# CH32V467RET-R0.net
KiCad netlist of a schematic drawn in Altium Designer
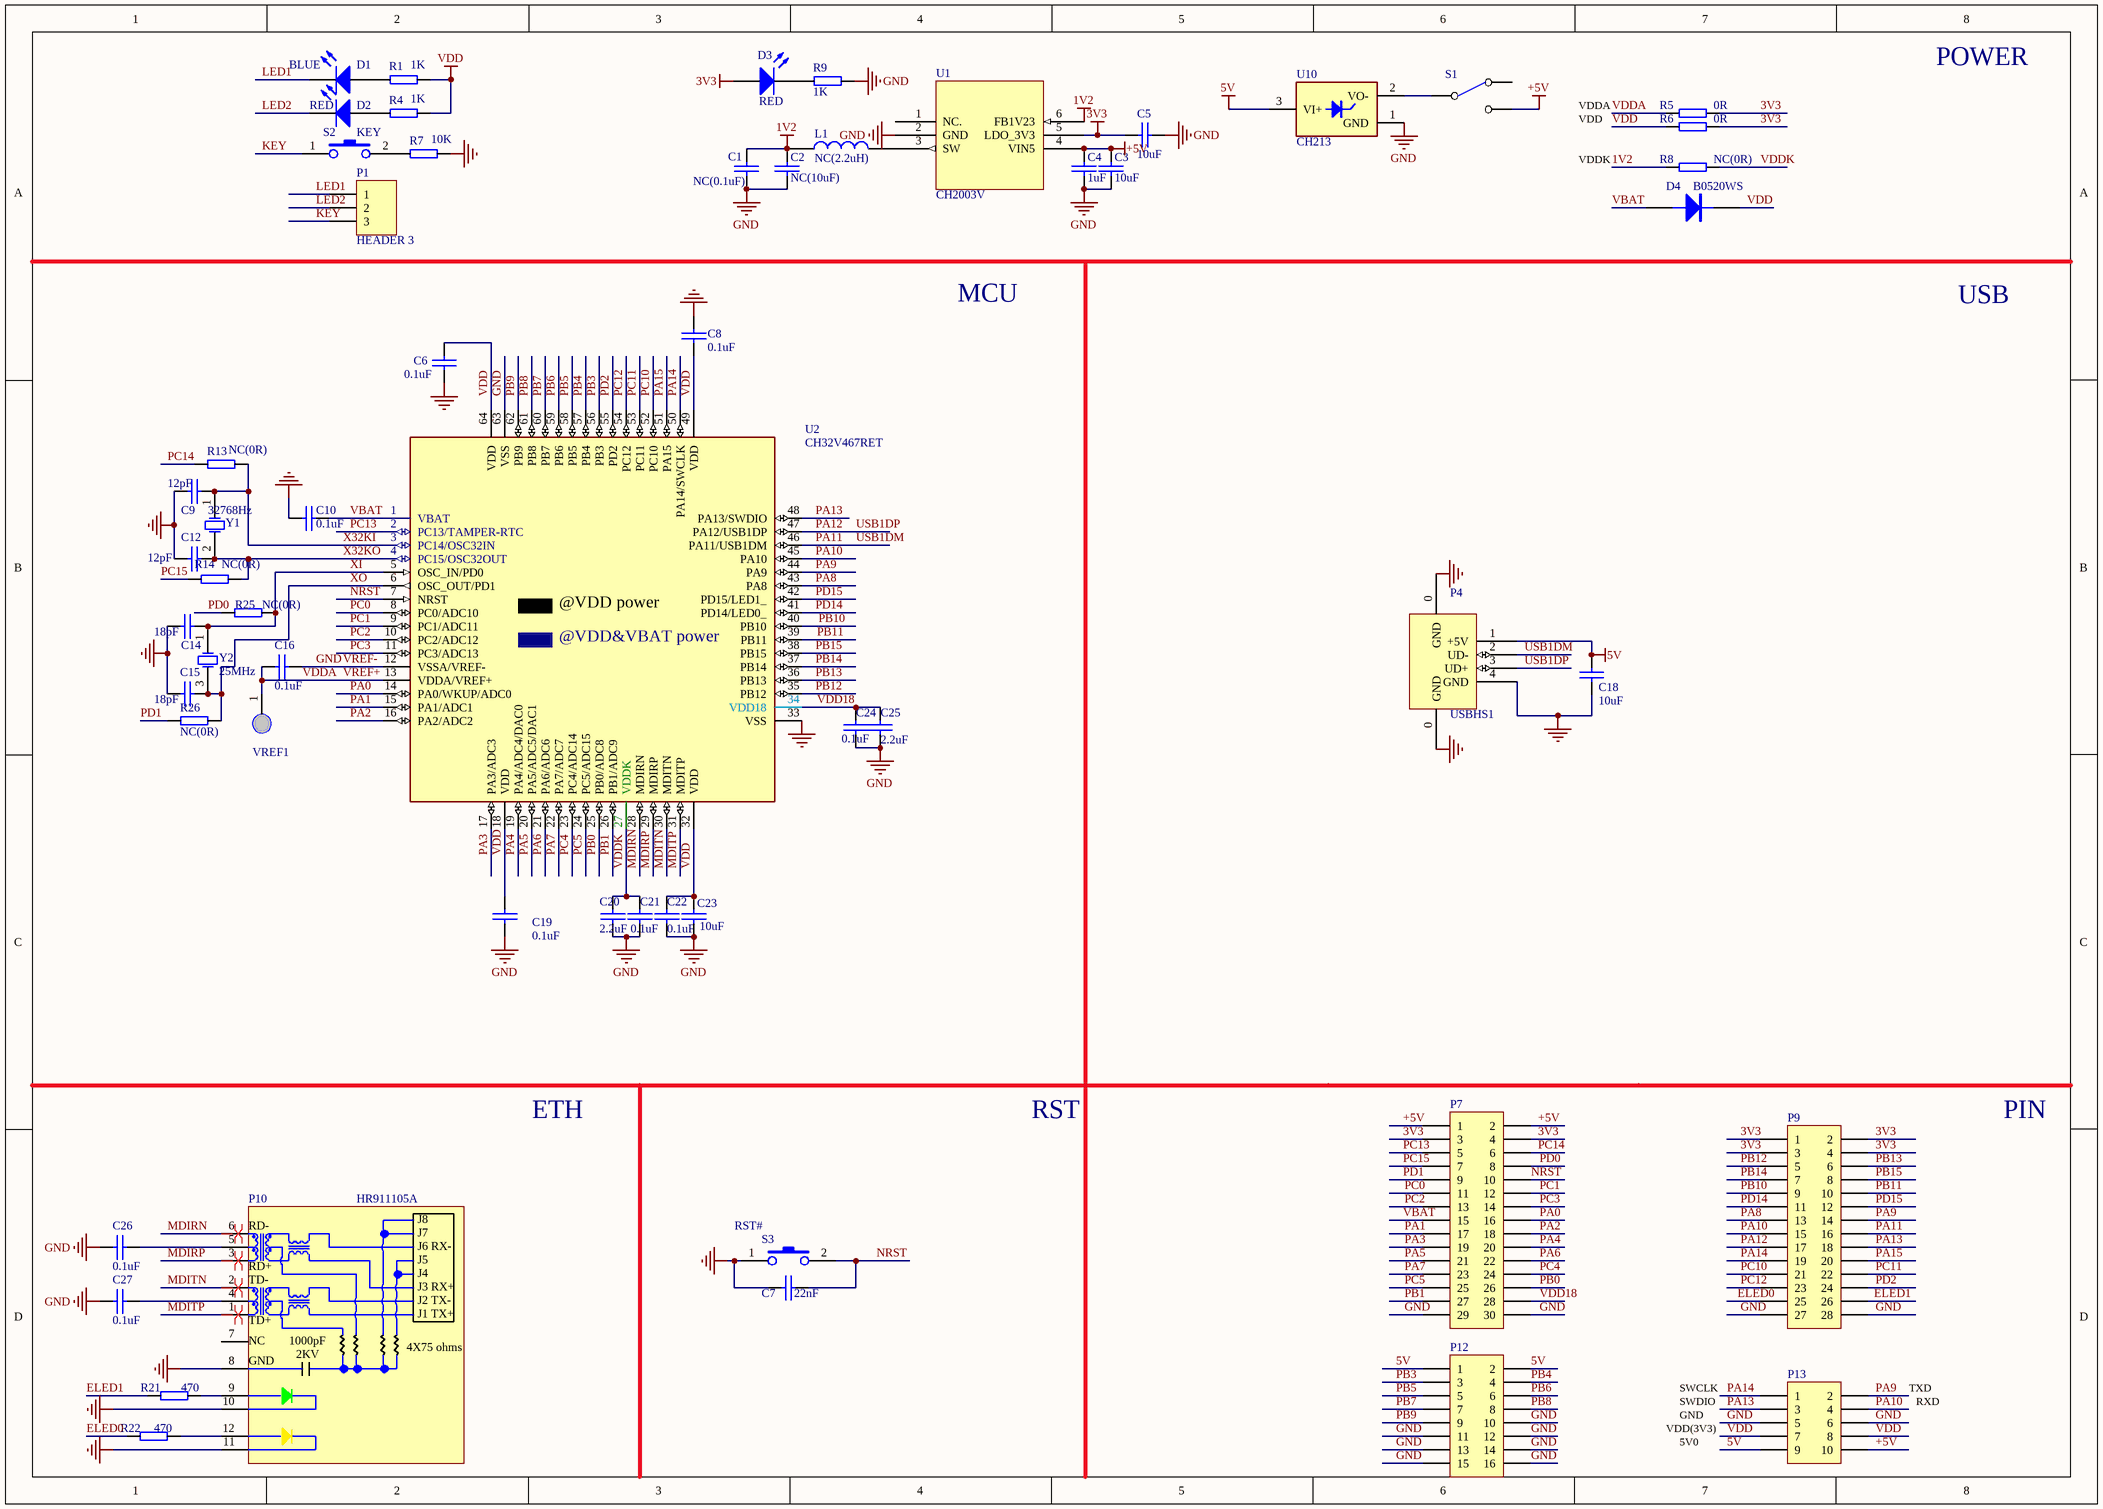
[diagram p0: CH32V467RET-R0.SchDoc]

(export (version "E")
  (design (tool "Eeschema 10.0.6"))
  (components
    (comp (ref "C1")
      (value "NC(0.1uF)")
      (footprint "0402_C")
      (description "Capacitor")
      (libsource (lib "") (part "CAP_1"))
    )
    (comp (ref "C2")
      (value "NC(10uF)")
      (footprint "0603_C")
      (description "Capacitor")
      (libsource (lib "*") (part "CAP"))
    )
    (comp (ref "C3")
      (value "10uF")
      (footprint "0603_C")
      (description "Capacitor")
      (libsource (lib "*") (part "CAP"))
    )
    (comp (ref "C4")
      (value "1uF")
      (footprint "0402_C")
      (description "Capacitor")
      (libsource (lib "") (part "CAP_1"))
    )
    (comp (ref "C5")
      (value "10uF")
      (footprint "0603_C")
      (description "Capacitor")
      (libsource (lib "*") (part "CAP"))
    )
    (comp (ref "C6")
      (value "0.1uF")
      (footprint "0402_C")
      (description "Capacitor")
      (libsource (lib "*") (part "CAP"))
    )
    (comp (ref "C7")
      (value "22nF")
      (footprint "0402_C")
      (description "Capacitor")
      (libsource (lib "") (part "CAP_2"))
    )
    (comp (ref "C8")
      (value "0.1uF")
      (footprint "0402_C")
      (description "Capacitor")
      (libsource (lib "*") (part "CAP"))
    )
    (comp (ref "C9")
      (value "12pF")
      (footprint "0402_C")
      (description "Capacitor")
      (libsource (lib "*") (part "CAP"))
    )
    (comp (ref "C10")
      (value "0.1uF")
      (footprint "0402_C")
      (description "Capacitor")
      (libsource (lib "*") (part "CAP"))
    )
    (comp (ref "C12")
      (value "12pF")
      (footprint "0402_C")
      (description "Capacitor")
      (libsource (lib "*") (part "CAP"))
    )
    (comp (ref "C14")
      (value "18pF")
      (footprint "0402_C")
      (description "Capacitor")
      (libsource (lib "*") (part "CAP"))
    )
    (comp (ref "C15")
      (value "18pF")
      (footprint "0402_C")
      (description "Capacitor")
      (libsource (lib "*") (part "CAP"))
    )
    (comp (ref "C16")
      (value "0.1uF")
      (footprint "0402_C")
      (description "Capacitor")
      (libsource (lib "*") (part "CAP"))
    )
    (comp (ref "C18")
      (value "10uF")
      (footprint "0603_C")
      (description "Capacitor")
      (libsource (lib "") (part "CAP_2"))
    )
    (comp (ref "C19")
      (value "0.1uF")
      (footprint "0402_C")
      (description "Capacitor")
      (libsource (lib "*") (part "CAP"))
    )
    (comp (ref "C20")
      (value "2.2uF")
      (footprint "0402_C")
      (description "Capacitor")
      (libsource (lib "*") (part "CAP"))
    )
    (comp (ref "C21")
      (value "0.1uF")
      (footprint "0402_C")
      (description "Capacitor")
      (libsource (lib "*") (part "CAP"))
    )
    (comp (ref "C22")
      (value "0.1uF")
      (footprint "0402_C")
      (description "Capacitor")
      (libsource (lib "*") (part "CAP"))
    )
    (comp (ref "C23")
      (value "10uF")
      (footprint "0603_C")
      (description "Capacitor")
      (libsource (lib "wch_sch_others") (part "CAP"))
    )
    (comp (ref "C24")
      (value "0.1uF")
      (footprint "0402_C")
      (description "Capacitor")
      (libsource (lib "*") (part "CAP"))
    )
    (comp (ref "C25")
      (value "2.2uF")
      (footprint "0402_C")
      (description "Capacitor")
      (libsource (lib "*") (part "CAP"))
    )
    (comp (ref "C26")
      (value "0.1uF")
      (footprint "0402_C")
      (description "Capacitor")
      (libsource (lib "wch_sch_others") (part "CAP"))
    )
    (comp (ref "C27")
      (value "0.1uF")
      (footprint "0402_C")
      (description "Capacitor")
      (libsource (lib "wch_sch_others") (part "CAP"))
    )
    (comp (ref "D1")
      (value "BLUE")
      (footprint "0603+")
      (description "Typical INFRARED GaAs LED")
      (fields (field (name "PUBLISHER") "Altium Limited"))
      (libsource (lib "*") (part "LED0"))
    )
    (comp (ref "D2")
      (value "RED")
      (footprint "0603+")
      (description "Typical INFRARED GaAs LED")
      (fields (field (name "PUBLISHER") "Altium Limited"))
      (libsource (lib "*") (part "LED0"))
    )
    (comp (ref "D3")
      (value "RED")
      (footprint "0603+")
      (description "Typical INFRARED GaAs LED")
      (fields (field (name "PUBLISHER") "Altium Limited"))
      (libsource (lib "*") (part "LED0"))
    )
    (comp (ref "D4")
      (value "B0520WS")
      (footprint "SOD-323")
      (description "Diode")
      (libsource (lib "*") (part "DIODE"))
    )
    (comp (ref "L1") (value "NC(2.2uH)") (footprint "CD32") (libsource (lib "*") (part "INDUCTOR")))
    (comp (ref "P1")
      (value "HEADER 3")
      (footprint "SIP3-2.54MM")
      (description "Header, 3-Pin")
      (libsource (lib "wch_sch_others") (part "HEADER 3"))
    )
    (comp (ref "P4")
      (value "USBHS1")
      (footprint "USBAF")
      (description "USB Port")
      (libsource (lib "*") (part "USB"))
    )
    (comp (ref "P7")
      (value "HEADER 15x2")
      (footprint "MYPCB:IDC30-2.54MM")
      (description "Header, 15-Pin, Dual row")
      (libsource (lib "wch_sch_others") (part "HEADER 15x2"))
    )
    (comp (ref "P9")
      (value "HEADER 14x2")
      (footprint "MYPCB:IDC28-2.54MM")
      (description "Header, 14-Pin, Dual row")
      (libsource (lib "wch_sch_others") (part "HEADER 14x2"))
    )
    (comp (ref "P10") (value "HR911105A") (footprint "HR911105A") (libsource (lib "*") (part "HR911105A")))
    (comp (ref "P12")
      (value "Ppin")
      (footprint "IDC16-2.54mm")
      (description "Header, 8-Pin, Dual row, Right Angle")
      (fields (field (name "PUBLISHER") "Altium Limited"))
      (libsource (lib "Miscellaneous Connectors") (part "Header 8X2H"))
    )
    (comp (ref "P13")
      (value "LINK")
      (footprint "IDC10-2.54mm")
      (description "Header, 5-Pin, Dual row, Right Angle")
      (fields (field (name "PUBLISHER") "Altium Limited"))
      (libsource (lib "Miscellaneous Connectors") (part "Header 5X2H"))
    )
    (comp (ref "R1") (value "1K") (footprint "0402") (libsource (lib "wch_sch_others") (part "RES")))
    (comp (ref "R4") (value "1K") (footprint "0402") (libsource (lib "wch_sch_others") (part "RES")))
    (comp (ref "R5") (value "0R") (footprint "0402") (libsource (lib "*") (part "R")))
    (comp (ref "R6") (value "0R") (footprint "0402") (libsource (lib "*") (part "R")))
    (comp (ref "R7") (value "10K") (footprint "0402") (libsource (lib "wch_sch_others") (part "RES")))
    (comp (ref "R8") (value "NC(0R)") (footprint "0402") (libsource (lib "*") (part "R")))
    (comp (ref "R9") (value "1K") (footprint "0402") (libsource (lib "wch_sch_others") (part "RES")))
    (comp (ref "R13") (value "NC(0R)") (footprint "0402") (libsource (lib "wch_sch_others") (part "RES")))
    (comp (ref "R14") (value "NC(0R)") (footprint "0402") (libsource (lib "wch_sch_others") (part "RES")))
    (comp (ref "R21") (value "470") (footprint "0402") (libsource (lib "wch_sch_others") (part "RES")))
    (comp (ref "R22") (value "470") (footprint "0402") (libsource (lib "wch_sch_others") (part "RES")))
    (comp (ref "R25") (value "NC(0R)") (footprint "0402") (libsource (lib "wch_sch_others") (part "RES")))
    (comp (ref "R26") (value "NC(0R)") (footprint "0402") (libsource (lib "wch_sch_others") (part "RES")))
    (comp (ref "S1") (value "SW SPDT") (footprint "SW1") (libsource (lib "*") (part "SW SPDT")))
    (comp (ref "S2")
      (value "KEY")
      (footprint "SMD_6.1x3.65x2.5mm-KEY")
      (libsource (lib "wch_sch_others") (part "KEY1"))
    )
    (comp (ref "S3")
      (value "RST#")
      (footprint "SMD_6.1x3.65x2.5mm-KEY")
      (libsource (lib "wch_sch_others") (part "KEY1"))
    )
    (comp (ref "U1")
      (value "CH2003V")
      (footprint "SOT-23-6")
      (description "Step-Down DC-DC Converter, 5V input, 1.23V * 800mA output, with LDO 3.3V * 200mA")
      (libsource (lib "CHXXX") (part "CH2003V"))
    )
    (comp (ref "U2")
      (value "CH32V467RET")
      (footprint "LQFP64_7X7")
      (description "RISC-V FPU HD-MCU, 175MHz, USB_480M, 100M Ethernet & Phy, CAN, ADC, DAC, SRAM")
      (libsource (lib "CHXXX") (part "CH32V467RET"))
    )
    (comp (ref "U10")
      (value "CH213")
      (footprint "SOT-23-3")
      (description "Ideal Diode 5V*1A")
      (libsource (lib "CHXXX") (part "CH213E"))
    )
    (comp (ref "VREF1")
      (value "PAD")
      (footprint "TESTPOINT1")
      (description "焊盘")
      (libsource (lib "wch_sch_others") (part "PAD"))
    )
    (comp (ref "Y1")
      (value "32768Hz")
      (footprint "FC-135")
      (description "Crystal Oscillator")
      (fields (field (name "PUBLISHER") "Altium Limited"))
      (libsource (lib "*") (part "XTAL"))
    )
    (comp (ref "Y2")
      (value "25MHz")
      (footprint "XT3225")
      (description "Crystal Oscillator")
      (fields (field (name "PUBLISHER") "Altium Limited"))
      (libsource (lib "") (part "XTAL_1"))
    )
  )
  (nets
    (net (code "1") (name "+5V") (class "Default")
      (node (ref "C3") (pin "2") (pinfunction "2_2") (pintype "passive"))
      (node (ref "C4") (pin "2") (pinfunction "2_2") (pintype "passive"))
      (node (ref "P13") (pin "10") (pinfunction "10_10") (pintype "passive"))
      (node (ref "P7") (pin "1") (pinfunction "1_1") (pintype "passive"))
      (node (ref "P7") (pin "2") (pinfunction "2_2") (pintype "passive"))
      (node (ref "S1") (pin "2") (pinfunction "NC_2") (pintype "passive"))
      (node (ref "U1") (pin "4") (pinfunction "VIN5_4") (pintype "power_in"))
    )
    (net (code "3") (name "/ELED0") (class "Default")
      (node (ref "P9") (pin "25") (pinfunction "25_25") (pintype "passive"))
      (node (ref "R22") (pin "1") (pintype "passive"))
    )
    (net (code "4") (name "/ELED1") (class "Default")
      (node (ref "P9") (pin "26") (pinfunction "26_26") (pintype "passive"))
      (node (ref "R21") (pin "1") (pintype "passive"))
    )
    (net (code "5") (name "/KEY") (class "Default")
      (node (ref "P1") (pin "3") (pinfunction "3_3") (pintype "passive"))
      (node (ref "S2") (pin "1") (pinfunction "1_1") (pintype "passive"))
    )
    (net (code "6") (name "/LED1") (class "Default")
      (node (ref "D1") (pin "2") (pinfunction "K_2") (pintype "passive"))
      (node (ref "P1") (pin "1") (pinfunction "1_1") (pintype "passive"))
    )
    (net (code "7") (name "/LED2") (class "Default")
      (node (ref "D2") (pin "2") (pinfunction "K_2") (pintype "passive"))
      (node (ref "P1") (pin "2") (pinfunction "2_2") (pintype "passive"))
    )
    (net (code "8") (name "/MDIRN") (class "Default")
      (node (ref "P10") (pin "6") (pintype "passive"))
      (node (ref "U2") (pin "28") (pinfunction "MDIRN_28") (pintype "bidirectional"))
    )
    (net (code "9") (name "/MDIRP") (class "Default")
      (node (ref "P10") (pin "3") (pintype "passive"))
      (node (ref "U2") (pin "29") (pinfunction "MDIRP_29") (pintype "bidirectional"))
    )
    (net (code "10") (name "/MDITN") (class "Default")
      (node (ref "P10") (pin "2") (pintype "passive"))
      (node (ref "U2") (pin "30") (pinfunction "MDITN_30") (pintype "bidirectional"))
    )
    (net (code "11") (name "/MDITP") (class "Default")
      (node (ref "P10") (pin "1") (pintype "passive"))
      (node (ref "U2") (pin "31") (pinfunction "MDITP_31") (pintype "bidirectional"))
    )
    (net (code "12") (name "/NRST") (class "Default")
      (node (ref "C7") (pin "2") (pinfunction "2_2") (pintype "passive"))
      (node (ref "P7") (pin "10") (pinfunction "10_10") (pintype "passive"))
      (node (ref "S3") (pin "2") (pinfunction "2_2") (pintype "passive"))
      (node (ref "U2") (pin "7") (pinfunction "NRST_7") (pintype "input"))
    )
    (net (code "13") (name "/PA0") (class "Default")
      (node (ref "P7") (pin "16") (pinfunction "16_16") (pintype "passive"))
      (node (ref "U2") (pin "14") (pinfunction "PA0/WKUP/ADC0_14") (pintype "bidirectional"))
    )
    (net (code "14") (name "/PA1") (class "Default")
      (node (ref "P7") (pin "17") (pinfunction "17_17") (pintype "passive"))
      (node (ref "U2") (pin "15") (pinfunction "PA1/ADC1_15") (pintype "bidirectional"))
    )
    (net (code "15") (name "/PA2") (class "Default")
      (node (ref "P7") (pin "18") (pinfunction "18_18") (pintype "passive"))
      (node (ref "U2") (pin "16") (pinfunction "PA2/ADC2_16") (pintype "bidirectional"))
    )
    (net (code "16") (name "/PA3") (class "Default")
      (node (ref "P7") (pin "19") (pinfunction "19_19") (pintype "passive"))
      (node (ref "U2") (pin "17") (pinfunction "PA3/ADC3_17") (pintype "bidirectional"))
    )
    (net (code "17") (name "/PA4") (class "Default")
      (node (ref "P7") (pin "20") (pinfunction "20_20") (pintype "passive"))
      (node (ref "U2") (pin "19") (pinfunction "PA4/ADC4/DAC0_19") (pintype "bidirectional"))
    )
    (net (code "18") (name "/PA5") (class "Default")
      (node (ref "P7") (pin "21") (pinfunction "21_21") (pintype "passive"))
      (node (ref "U2") (pin "20") (pinfunction "PA5/ADC5/DAC1_20") (pintype "bidirectional"))
    )
    (net (code "19") (name "/PA6") (class "Default")
      (node (ref "P7") (pin "22") (pinfunction "22_22") (pintype "passive"))
      (node (ref "U2") (pin "21") (pinfunction "PA6/ADC6_21") (pintype "bidirectional"))
    )
    (net (code "20") (name "/PA7") (class "Default")
      (node (ref "P7") (pin "23") (pinfunction "23_23") (pintype "passive"))
      (node (ref "U2") (pin "22") (pinfunction "PA7/ADC7_22") (pintype "bidirectional"))
    )
    (net (code "21") (name "/PA8") (class "Default")
      (node (ref "P9") (pin "13") (pinfunction "13_13") (pintype "passive"))
      (node (ref "U2") (pin "43") (pinfunction "PA8_43") (pintype "bidirectional"))
    )
    (net (code "22") (name "/PA9") (class "Default")
      (node (ref "P13") (pin "2") (pinfunction "2_2") (pintype "passive"))
      (node (ref "P9") (pin "14") (pinfunction "14_14") (pintype "passive"))
      (node (ref "U2") (pin "44") (pinfunction "PA9_44") (pintype "bidirectional"))
    )
    (net (code "23") (name "/PA10") (class "Default")
      (node (ref "P13") (pin "4") (pinfunction "4_4") (pintype "passive"))
      (node (ref "P9") (pin "15") (pinfunction "15_15") (pintype "passive"))
      (node (ref "U2") (pin "45") (pinfunction "PA10_45") (pintype "bidirectional"))
    )
    (net (code "24") (name "/PA11") (class "Default")
      (node (ref "P4") (pin "2") (pinfunction "UD-_2") (pintype "bidirectional"))
      (node (ref "P9") (pin "16") (pinfunction "16_16") (pintype "passive"))
      (node (ref "U2") (pin "46") (pinfunction "PA11/USB1DM_46") (pintype "bidirectional"))
    )
    (net (code "25") (name "/PA12") (class "Default")
      (node (ref "P4") (pin "3") (pinfunction "UD+_3") (pintype "bidirectional"))
      (node (ref "P9") (pin "17") (pinfunction "17_17") (pintype "passive"))
      (node (ref "U2") (pin "47") (pinfunction "PA12/USB1DP_47") (pintype "bidirectional"))
    )
    (net (code "26") (name "/PA13") (class "Default")
      (node (ref "P13") (pin "3") (pinfunction "3_3") (pintype "passive"))
      (node (ref "P9") (pin "18") (pinfunction "18_18") (pintype "passive"))
      (node (ref "U2") (pin "48") (pinfunction "PA13/SWDIO_48") (pintype "bidirectional"))
    )
    (net (code "27") (name "/PA14") (class "Default")
      (node (ref "P13") (pin "1") (pinfunction "1_1") (pintype "passive"))
      (node (ref "P9") (pin "19") (pinfunction "19_19") (pintype "passive"))
      (node (ref "U2") (pin "50") (pinfunction "PA14/SWCLK_50") (pintype "bidirectional"))
    )
    (net (code "28") (name "/PA15") (class "Default")
      (node (ref "P9") (pin "20") (pinfunction "20_20") (pintype "passive"))
      (node (ref "U2") (pin "51") (pinfunction "PA15_51") (pintype "bidirectional"))
    )
    (net (code "29") (name "/PB0") (class "Default")
      (node (ref "P7") (pin "26") (pinfunction "26_26") (pintype "passive"))
      (node (ref "U2") (pin "25") (pinfunction "PB0/ADC8_25") (pintype "bidirectional"))
    )
    (net (code "30") (name "/PB1") (class "Default")
      (node (ref "P7") (pin "27") (pinfunction "27_27") (pintype "passive"))
      (node (ref "U2") (pin "26") (pinfunction "PB1/ADC9_26") (pintype "bidirectional"))
    )
    (net (code "31") (name "/PB3") (class "Default")
      (node (ref "P12") (pin "3") (pinfunction "3_3") (pintype "passive"))
      (node (ref "U2") (pin "56") (pinfunction "PB3_56") (pintype "bidirectional"))
    )
    (net (code "32") (name "/PB4") (class "Default")
      (node (ref "P12") (pin "4") (pinfunction "4_4") (pintype "passive"))
      (node (ref "U2") (pin "57") (pinfunction "PB4_57") (pintype "bidirectional"))
    )
    (net (code "33") (name "/PB5") (class "Default")
      (node (ref "P12") (pin "5") (pinfunction "5_5") (pintype "passive"))
      (node (ref "U2") (pin "58") (pinfunction "PB5_58") (pintype "bidirectional"))
    )
    (net (code "34") (name "/PB6") (class "Default")
      (node (ref "P12") (pin "6") (pinfunction "6_6") (pintype "passive"))
      (node (ref "U2") (pin "59") (pinfunction "PB6_59") (pintype "bidirectional"))
    )
    (net (code "35") (name "/PB7") (class "Default")
      (node (ref "P12") (pin "7") (pinfunction "7_7") (pintype "passive"))
      (node (ref "U2") (pin "60") (pinfunction "PB7_60") (pintype "bidirectional"))
    )
    (net (code "36") (name "/PB8") (class "Default")
      (node (ref "P12") (pin "8") (pinfunction "8_8") (pintype "passive"))
      (node (ref "U2") (pin "61") (pinfunction "PB8_61") (pintype "bidirectional"))
    )
    (net (code "37") (name "/PB9") (class "Default")
      (node (ref "P12") (pin "9") (pinfunction "9_9") (pintype "passive"))
      (node (ref "U2") (pin "62") (pinfunction "PB9_62") (pintype "bidirectional"))
    )
    (net (code "38") (name "/PB10") (class "Default")
      (node (ref "P9") (pin "9") (pinfunction "9_9") (pintype "passive"))
      (node (ref "U2") (pin "40") (pinfunction "PB10_40") (pintype "bidirectional"))
    )
    (net (code "39") (name "/PB11") (class "Default")
      (node (ref "P9") (pin "10") (pinfunction "10_10") (pintype "passive"))
      (node (ref "U2") (pin "39") (pinfunction "PB11_39") (pintype "bidirectional"))
    )
    (net (code "40") (name "/PB12") (class "Default")
      (node (ref "P9") (pin "5") (pinfunction "5_5") (pintype "passive"))
      (node (ref "U2") (pin "35") (pinfunction "PB12_35") (pintype "bidirectional"))
    )
    (net (code "41") (name "/PB13") (class "Default")
      (node (ref "P9") (pin "6") (pinfunction "6_6") (pintype "passive"))
      (node (ref "U2") (pin "36") (pinfunction "PB13_36") (pintype "bidirectional"))
    )
    (net (code "42") (name "/PB14") (class "Default")
      (node (ref "P9") (pin "7") (pinfunction "7_7") (pintype "passive"))
      (node (ref "U2") (pin "37") (pinfunction "PB14_37") (pintype "bidirectional"))
    )
    (net (code "43") (name "/PB15") (class "Default")
      (node (ref "P9") (pin "8") (pinfunction "8_8") (pintype "passive"))
      (node (ref "U2") (pin "38") (pinfunction "PB15_38") (pintype "bidirectional"))
    )
    (net (code "44") (name "/PC0") (class "Default")
      (node (ref "P7") (pin "11") (pinfunction "11_11") (pintype "passive"))
      (node (ref "U2") (pin "8") (pinfunction "PC0/ADC10_8") (pintype "bidirectional"))
    )
    (net (code "45") (name "/PC1") (class "Default")
      (node (ref "P7") (pin "12") (pinfunction "12_12") (pintype "passive"))
      (node (ref "U2") (pin "9") (pinfunction "PC1/ADC11_9") (pintype "bidirectional"))
    )
    (net (code "46") (name "/PC2") (class "Default")
      (node (ref "P7") (pin "13") (pinfunction "13_13") (pintype "passive"))
      (node (ref "U2") (pin "10") (pinfunction "PC2/ADC12_10") (pintype "bidirectional"))
    )
    (net (code "47") (name "/PC3") (class "Default")
      (node (ref "P7") (pin "14") (pinfunction "14_14") (pintype "passive"))
      (node (ref "U2") (pin "11") (pinfunction "PC3/ADC13_11") (pintype "bidirectional"))
    )
    (net (code "48") (name "/PC4") (class "Default")
      (node (ref "P7") (pin "24") (pinfunction "24_24") (pintype "passive"))
      (node (ref "U2") (pin "23") (pinfunction "PC4/ADC14_23") (pintype "bidirectional"))
    )
    (net (code "49") (name "/PC5") (class "Default")
      (node (ref "P7") (pin "25") (pinfunction "25_25") (pintype "passive"))
      (node (ref "U2") (pin "24") (pinfunction "PC5/ADC15_24") (pintype "bidirectional"))
    )
    (net (code "50") (name "/PC10") (class "Default")
      (node (ref "P9") (pin "21") (pinfunction "21_21") (pintype "passive"))
      (node (ref "U2") (pin "52") (pinfunction "PC10_52") (pintype "bidirectional"))
    )
    (net (code "51") (name "/PC11") (class "Default")
      (node (ref "P9") (pin "22") (pinfunction "22_22") (pintype "passive"))
      (node (ref "U2") (pin "53") (pinfunction "PC11_53") (pintype "bidirectional"))
    )
    (net (code "52") (name "/PC12") (class "Default")
      (node (ref "P9") (pin "23") (pinfunction "23_23") (pintype "passive"))
      (node (ref "U2") (pin "54") (pinfunction "PC12_54") (pintype "bidirectional"))
    )
    (net (code "53") (name "/PC13") (class "Default")
      (node (ref "P7") (pin "5") (pinfunction "5_5") (pintype "passive"))
      (node (ref "U2") (pin "2") (pinfunction "PC13/TAMPER-RTC_2") (pintype "bidirectional"))
    )
    (net (code "54") (name "/PC14") (class "Default")
      (node (ref "P7") (pin "6") (pinfunction "6_6") (pintype "passive"))
      (node (ref "R13") (pin "1") (pintype "passive"))
    )
    (net (code "55") (name "/PC15") (class "Default")
      (node (ref "P7") (pin "7") (pinfunction "7_7") (pintype "passive"))
      (node (ref "R14") (pin "1") (pintype "passive"))
    )
    (net (code "56") (name "/PD0") (class "Default")
      (node (ref "P7") (pin "8") (pinfunction "8_8") (pintype "passive"))
      (node (ref "R25") (pin "1") (pintype "passive"))
    )
    (net (code "57") (name "/PD1") (class "Default")
      (node (ref "P7") (pin "9") (pinfunction "9_9") (pintype "passive"))
      (node (ref "R26") (pin "2") (pintype "passive"))
    )
    (net (code "58") (name "/PD2") (class "Default")
      (node (ref "P9") (pin "24") (pinfunction "24_24") (pintype "passive"))
      (node (ref "U2") (pin "55") (pinfunction "PD2_55") (pintype "bidirectional"))
    )
    (net (code "59") (name "/PD14") (class "Default")
      (node (ref "P9") (pin "11") (pinfunction "11_11") (pintype "passive"))
      (node (ref "U2") (pin "41") (pinfunction "PD14/LED0__41") (pintype "bidirectional"))
    )
    (net (code "60") (name "/PD15") (class "Default")
      (node (ref "P9") (pin "12") (pinfunction "12_12") (pintype "passive"))
      (node (ref "U2") (pin "42") (pinfunction "PD15/LED1__42") (pintype "bidirectional"))
    )
    (net (code "61") (name "/VBAT") (class "Default")
      (node (ref "C10") (pin "2") (pinfunction "2_2") (pintype "passive"))
      (node (ref "D4") (pin "1") (pinfunction "A_1") (pintype "passive"))
      (node (ref "P7") (pin "15") (pinfunction "15_15") (pintype "passive"))
      (node (ref "U2") (pin "1") (pinfunction "VBAT_1") (pintype "power_in"))
    )
    (net (code "62") (name "/VDD18") (class "Default")
      (node (ref "C24") (pin "2") (pinfunction "2_2") (pintype "passive"))
      (node (ref "C25") (pin "2") (pinfunction "2_2") (pintype "passive"))
      (node (ref "P7") (pin "28") (pinfunction "28_28") (pintype "passive"))
      (node (ref "U2") (pin "34") (pinfunction "VDD18_34") (pintype "power_in"))
    )
    (net (code "63") (name "/VDDA") (class "Default")
      (node (ref "C16") (pin "1") (pinfunction "1_1") (pintype "passive"))
      (node (ref "R5") (pin "2") (pinfunction "2_2") (pintype "passive"))
      (node (ref "U2") (pin "13") (pinfunction "VDDA/VREF+_13") (pintype "power_in"))
      (node (ref "VREF1") (pin "1") (pintype "passive"))
    )
    (net (code "64") (name "/VDDK") (class "Default")
      (node (ref "C20") (pin "2") (pinfunction "2_2") (pintype "passive"))
      (node (ref "C21") (pin "2") (pinfunction "2_2") (pintype "passive"))
      (node (ref "R8") (pin "1") (pinfunction "1_1") (pintype "passive"))
      (node (ref "U2") (pin "27") (pinfunction "VDDK_27") (pintype "power_in"))
    )
    (net (code "65") (name "/X32KI") (class "Default")
      (node (ref "C9") (pin "2") (pinfunction "2_2") (pintype "passive"))
      (node (ref "R13") (pin "2") (pintype "passive"))
      (node (ref "U2") (pin "3") (pinfunction "PC14/OSC32IN_3") (pintype "bidirectional"))
      (node (ref "Y1") (pin "1") (pinfunction "OSC1_1") (pintype "passive"))
    )
    (net (code "66") (name "/X32KO") (class "Default")
      (node (ref "C12") (pin "2") (pinfunction "2_2") (pintype "passive"))
      (node (ref "R14") (pin "2") (pintype "passive"))
      (node (ref "U2") (pin "4") (pinfunction "PC15/OSC32OUT_4") (pintype "bidirectional"))
      (node (ref "Y1") (pin "2") (pinfunction "OSC2_2") (pintype "passive"))
    )
    (net (code "67") (name "/XI") (class "Default")
      (node (ref "C14") (pin "2") (pinfunction "2_2") (pintype "passive"))
      (node (ref "R25") (pin "2") (pintype "passive"))
      (node (ref "U2") (pin "5") (pinfunction "OSC_IN/PD0_5") (pintype "input"))
      (node (ref "Y2") (pin "1") (pinfunction "OSC1_1") (pintype "passive"))
    )
    (net (code "68") (name "/XO") (class "Default")
      (node (ref "C15") (pin "2") (pinfunction "2_2") (pintype "passive"))
      (node (ref "R26") (pin "1") (pintype "passive"))
      (node (ref "U2") (pin "6") (pinfunction "OSC_OUT/PD1_6") (pintype "output"))
      (node (ref "Y2") (pin "3") (pinfunction "OSC2_3") (pintype "passive"))
    )
    (net (code "69") (name "1V2") (class "Default")
      (node (ref "C1") (pin "2") (pinfunction "2_2") (pintype "passive"))
      (node (ref "C2") (pin "2") (pinfunction "2_2") (pintype "passive"))
      (node (ref "L1") (pin "2") (pinfunction "2_2") (pintype "passive"))
      (node (ref "R8") (pin "2") (pinfunction "2_2") (pintype "passive"))
      (node (ref "U1") (pin "6") (pinfunction "FB1V23_6") (pintype "input"))
    )
    (net (code "70") (name "3V3") (class "Default")
      (node (ref "C5") (pin "2") (pinfunction "2_2") (pintype "passive"))
      (node (ref "D3") (pin "1") (pinfunction "A_1") (pintype "passive"))
      (node (ref "P7") (pin "3") (pinfunction "3_3") (pintype "passive"))
      (node (ref "P7") (pin "4") (pinfunction "4_4") (pintype "passive"))
      (node (ref "P9") (pin "1") (pinfunction "1_1") (pintype "passive"))
      (node (ref "P9") (pin "2") (pinfunction "2_2") (pintype "passive"))
      (node (ref "P9") (pin "3") (pinfunction "3_3") (pintype "passive"))
      (node (ref "P9") (pin "4") (pinfunction "4_4") (pintype "passive"))
      (node (ref "R5") (pin "1") (pinfunction "1_1") (pintype "passive"))
      (node (ref "R6") (pin "1") (pinfunction "1_1") (pintype "passive"))
      (node (ref "U1") (pin "5") (pinfunction "LDO_3V3_5") (pintype "power_in"))
    )
    (net (code "71") (name "5V") (class "Default")
      (node (ref "C18") (pin "1") (pinfunction "1_1") (pintype "passive"))
      (node (ref "P12") (pin "1") (pinfunction "1_1") (pintype "passive"))
      (node (ref "P12") (pin "2") (pinfunction "2_2") (pintype "passive"))
      (node (ref "P13") (pin "9") (pinfunction "9_9") (pintype "passive"))
      (node (ref "P4") (pin "1") (pinfunction "+5V_1") (pintype "power_in"))
      (node (ref "U10") (pin "3") (pinfunction "VI+_3") (pintype "power_in"))
    )
    (net (code "72") (name "GND") (class "Default")
      (node (ref "C1") (pin "1") (pinfunction "1_1") (pintype "passive"))
      (node (ref "C10") (pin "1") (pinfunction "1_1") (pintype "passive"))
      (node (ref "C12") (pin "1") (pinfunction "1_1") (pintype "passive"))
      (node (ref "C14") (pin "1") (pinfunction "1_1") (pintype "passive"))
      (node (ref "C15") (pin "1") (pinfunction "1_1") (pintype "passive"))
      (node (ref "C16") (pin "2") (pinfunction "2_2") (pintype "passive"))
      (node (ref "C18") (pin "2") (pinfunction "2_2") (pintype "passive"))
      (node (ref "C19") (pin "1") (pinfunction "1_1") (pintype "passive"))
      (node (ref "C2") (pin "1") (pinfunction "1_1") (pintype "passive"))
      (node (ref "C20") (pin "1") (pinfunction "1_1") (pintype "passive"))
      (node (ref "C21") (pin "1") (pinfunction "1_1") (pintype "passive"))
      (node (ref "C22") (pin "1") (pinfunction "1_1") (pintype "passive"))
      (node (ref "C23") (pin "1") (pinfunction "1_1") (pintype "passive"))
      (node (ref "C24") (pin "1") (pinfunction "1_1") (pintype "passive"))
      (node (ref "C25") (pin "1") (pinfunction "1_1") (pintype "passive"))
      (node (ref "C26") (pin "1") (pinfunction "1_1") (pintype "passive"))
      (node (ref "C27") (pin "1") (pinfunction "1_1") (pintype "passive"))
      (node (ref "C3") (pin "1") (pinfunction "1_1") (pintype "passive"))
      (node (ref "C4") (pin "1") (pinfunction "1_1") (pintype "passive"))
      (node (ref "C5") (pin "1") (pinfunction "1_1") (pintype "passive"))
      (node (ref "C6") (pin "1") (pinfunction "1_1") (pintype "passive"))
      (node (ref "C7") (pin "1") (pinfunction "1_1") (pintype "passive"))
      (node (ref "C8") (pin "2") (pinfunction "2_2") (pintype "passive"))
      (node (ref "C9") (pin "1") (pinfunction "1_1") (pintype "passive"))
      (node (ref "P10") (pin "10") (pintype "passive"))
      (node (ref "P10") (pin "11") (pintype "passive"))
      (node (ref "P10") (pin "8") (pintype "passive"))
      (node (ref "P12") (pin "10") (pinfunction "10_10") (pintype "passive"))
      (node (ref "P12") (pin "11") (pinfunction "11_11") (pintype "passive"))
      (node (ref "P12") (pin "12") (pinfunction "12_12") (pintype "passive"))
      (node (ref "P12") (pin "13") (pinfunction "13_13") (pintype "passive"))
      (node (ref "P12") (pin "14") (pinfunction "14_14") (pintype "passive"))
      (node (ref "P12") (pin "15") (pinfunction "15_15") (pintype "passive"))
      (node (ref "P12") (pin "16") (pinfunction "16_16") (pintype "passive"))
      (node (ref "P13") (pin "5") (pinfunction "5_5") (pintype "passive"))
      (node (ref "P13") (pin "6") (pinfunction "6_6") (pintype "passive"))
      (node (ref "P4") (pin "0") (pinfunction "GND_0") (pintype "power_in"))
      (node (ref "P4") (pin "4") (pinfunction "GND_4") (pintype "power_in"))
      (node (ref "P7") (pin "29") (pinfunction "29_29") (pintype "passive"))
      (node (ref "P7") (pin "30") (pinfunction "30_30") (pintype "passive"))
      (node (ref "P9") (pin "27") (pinfunction "27_27") (pintype "passive"))
      (node (ref "P9") (pin "28") (pinfunction "28_28") (pintype "passive"))
      (node (ref "R7") (pin "1") (pintype "passive"))
      (node (ref "R9") (pin "2") (pintype "passive"))
      (node (ref "S3") (pin "1") (pinfunction "1_1") (pintype "passive"))
      (node (ref "U1") (pin "2") (pinfunction "GND_2") (pintype "power_in"))
      (node (ref "U10") (pin "1") (pinfunction "GND_1") (pintype "power_in"))
      (node (ref "U2") (pin "12") (pinfunction "VSSA/VREF-_12") (pintype "power_in"))
      (node (ref "U2") (pin "33") (pinfunction "VSS_33") (pintype "power_in"))
      (node (ref "U2") (pin "63") (pinfunction "VSS_63") (pintype "power_in"))
    )
    (net (code "73") (name "Net-(C26-Pad2)") (class "Default")
      (node (ref "C26") (pin "2") (pinfunction "2_2") (pintype "passive"))
      (node (ref "P10") (pin "5") (pintype "passive"))
    )
    (net (code "74") (name "Net-(C27-Pad2)") (class "Default")
      (node (ref "C27") (pin "2") (pinfunction "2_2") (pintype "passive"))
      (node (ref "P10") (pin "4") (pintype "passive"))
    )
    (net (code "75") (name "Net-(D1-A)") (class "Default")
      (node (ref "D1") (pin "1") (pinfunction "A_1") (pintype "passive"))
      (node (ref "R1") (pin "2") (pintype "passive"))
    )
    (net (code "76") (name "Net-(D2-A)") (class "Default")
      (node (ref "D2") (pin "1") (pinfunction "A_1") (pintype "passive"))
      (node (ref "R4") (pin "2") (pintype "passive"))
    )
    (net (code "77") (name "Net-(D3-K)") (class "Default")
      (node (ref "D3") (pin "2") (pinfunction "K_2") (pintype "passive"))
      (node (ref "R9") (pin "1") (pintype "passive"))
    )
    (net (code "78") (name "Net-(P10-Pad9)") (class "Default")
      (node (ref "P10") (pin "9") (pintype "passive"))
      (node (ref "R21") (pin "2") (pintype "passive"))
    )
    (net (code "79") (name "Net-(P10-Pad12)") (class "Default")
      (node (ref "P10") (pin "12") (pintype "passive"))
      (node (ref "R22") (pin "2") (pintype "passive"))
    )
    (net (code "80") (name "Net-(R7-Pad2)") (class "Default")
      (node (ref "R7") (pin "2") (pintype "passive"))
      (node (ref "S2") (pin "2") (pinfunction "2_2") (pintype "passive"))
    )
    (net (code "81") (name "Net-(S1-COMMON)") (class "Default")
      (node (ref "S1") (pin "1") (pinfunction "COMMON_1") (pintype "passive"))
      (node (ref "U10") (pin "2") (pinfunction "VO-_2") (pintype "power_in"))
    )
    (net (code "82") (name "Net-(U1-SW)") (class "Default")
      (node (ref "L1") (pin "1") (pinfunction "1_1") (pintype "passive"))
      (node (ref "U1") (pin "3") (pinfunction "SW_3") (pintype "output"))
    )
    (net (code "83") (name "VDD") (class "Default")
      (node (ref "C19") (pin "2") (pinfunction "2_2") (pintype "passive"))
      (node (ref "C22") (pin "2") (pinfunction "2_2") (pintype "passive"))
      (node (ref "C23") (pin "2") (pinfunction "2_2") (pintype "passive"))
      (node (ref "C6") (pin "2") (pinfunction "2_2") (pintype "passive"))
      (node (ref "C8") (pin "1") (pinfunction "1_1") (pintype "passive"))
      (node (ref "D4") (pin "2") (pinfunction "K_2") (pintype "passive"))
      (node (ref "P13") (pin "7") (pinfunction "7_7") (pintype "passive"))
      (node (ref "P13") (pin "8") (pinfunction "8_8") (pintype "passive"))
      (node (ref "R1") (pin "1") (pintype "passive"))
      (node (ref "R4") (pin "1") (pintype "passive"))
      (node (ref "R6") (pin "2") (pinfunction "2_2") (pintype "passive"))
      (node (ref "U2") (pin "18") (pinfunction "VDD_18") (pintype "power_in"))
      (node (ref "U2") (pin "32") (pinfunction "VDD_32") (pintype "power_in"))
      (node (ref "U2") (pin "49") (pinfunction "VDD_49") (pintype "power_in"))
      (node (ref "U2") (pin "64") (pinfunction "VDD_64") (pintype "power_in"))
    )
    (net (code "84") (name "unconnected-(P10-Pad7)") (class "Default")
      (node (ref "P10") (pin "7") (pintype "passive"))
    )
    (net (code "85") (name "unconnected-(S1-NO-Pad3)") (class "Default")
      (node (ref "S1") (pin "3") (pinfunction "NO_3") (pintype "passive"))
    )
    (net (code "86") (name "unconnected-(U1-NC.-Pad1)") (class "Default")
      (node (ref "U1") (pin "1") (pinfunction "NC._1") (pintype "passive"))
    )
  )
)
